# motorboardsurface.net
KiCad netlist of a schematic drawn in EAGLE
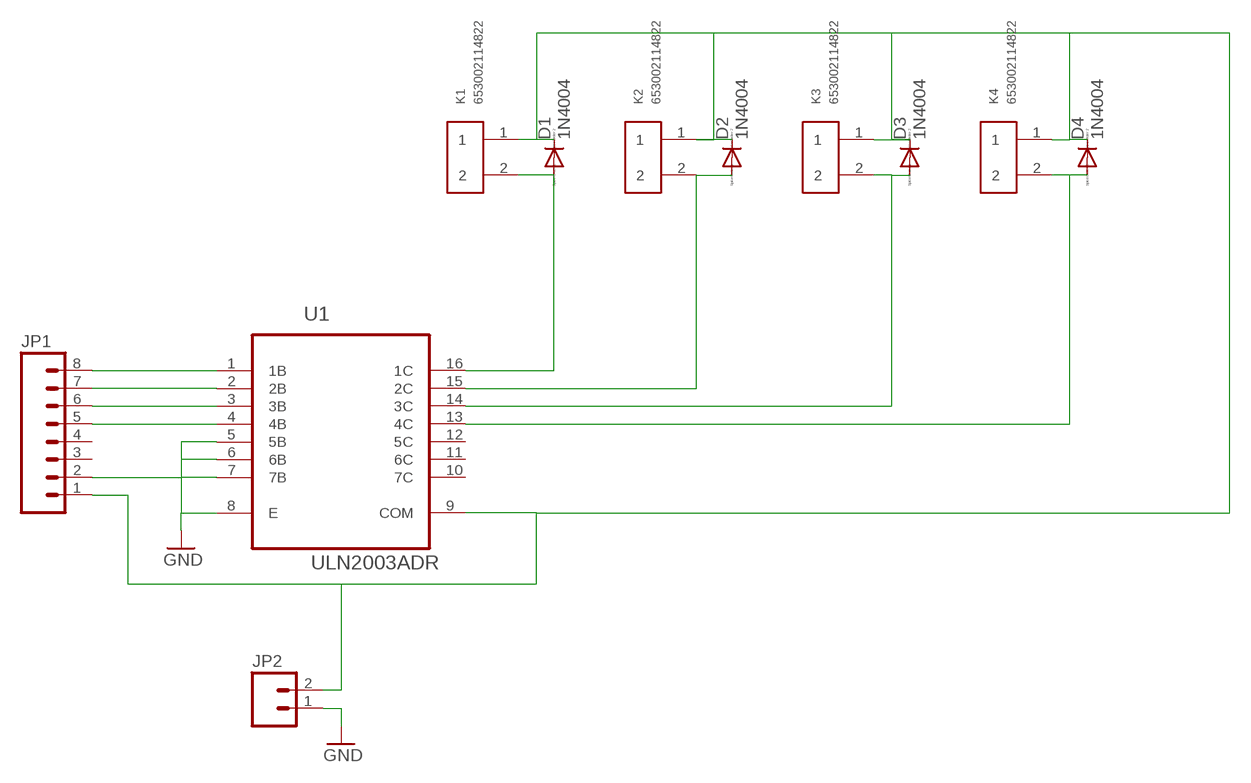
[diagram p0: schematic, sheet 1]

(export (version "E")
  (design (tool "Eeschema 10.0.6"))
  (components
    (comp (ref "D1")
      (value "1N4004")
      (footprint "eagle-import:DO41-10")
      (fields (field (name "MF") "NTE ELECTRONICS"))
      (libsource (lib "eagle-import") (part "1N4004"))
    )
    (comp (ref "D2")
      (value "1N4004")
      (footprint "eagle-import:DO41-10")
      (fields (field (name "MF") "NTE ELECTRONICS"))
      (libsource (lib "eagle-import") (part "1N4004"))
    )
    (comp (ref "D3")
      (value "1N4004")
      (footprint "eagle-import:DO41-10")
      (fields (field (name "MF") "NTE ELECTRONICS"))
      (libsource (lib "eagle-import") (part "1N4004"))
    )
    (comp (ref "D4")
      (value "1N4004")
      (footprint "eagle-import:DO41-10")
      (fields (field (name "MF") "NTE ELECTRONICS"))
      (libsource (lib "eagle-import") (part "1N4004"))
    )
    (comp (ref "JP1")
      (value "M08NO_SILK_FEMALE_PTH")
      (footprint "eagle-import:1X08_NO_SILK")
      (libsource (lib "eagle-import") (part "M08NO_SILK_FEMALE_PTH"))
    )
    (comp (ref "JP2")
      (value "M02LOCK_LONGPADS")
      (footprint "eagle-import:1X02_LOCK_LONGPADS")
      (libsource (lib "eagle-import") (part "M02LOCK_LONGPADS"))
    )
    (comp (ref "K1")
      (value "653002114822")
      (footprint "eagle-import:653002114822")
      (libsource (lib "eagle-import") (part "653002114822"))
    )
    (comp (ref "K2")
      (value "653002114822")
      (footprint "eagle-import:653002114822")
      (libsource (lib "eagle-import") (part "653002114822"))
    )
    (comp (ref "K3")
      (value "653002114822")
      (footprint "eagle-import:653002114822")
      (libsource (lib "eagle-import") (part "653002114822"))
    )
    (comp (ref "K4")
      (value "653002114822")
      (footprint "eagle-import:653002114822")
      (libsource (lib "eagle-import") (part "653002114822"))
    )
    (comp (ref "U1")
      (value "ULN2003ADR")
      (footprint "eagle-import:SOIC127P600X175-16N")
      (libsource (lib "eagle-import") (part "ULN2003ADR"))
    )
  )
  (nets
    (net (code "1") (name "GND") (class "Default")
      (node (ref "JP1") (pin "2") (pinfunction "2_2") (pintype "passive"))
      (node (ref "JP2") (pin "1") (pinfunction "1_1") (pintype "passive"))
      (node (ref "U1") (pin "5") (pinfunction "5B_5") (pintype "input"))
      (node (ref "U1") (pin "6") (pinfunction "6B_6") (pintype "input"))
      (node (ref "U1") (pin "7") (pinfunction "7B_7") (pintype "input"))
      (node (ref "U1") (pin "8") (pinfunction "E_8") (pintype "input"))
    )
    (net (code "2") (name "Net-(U1-1B)") (class "Default")
      (node (ref "JP1") (pin "8") (pinfunction "8_8") (pintype "passive"))
      (node (ref "U1") (pin "1") (pinfunction "1B_1") (pintype "input"))
    )
    (net (code "3") (name "Net-(U1-1C)") (class "Default")
      (node (ref "D1") (pin "A") (pinfunction "A_A") (pintype "passive"))
      (node (ref "K1") (pin "2") (pinfunction "2_2") (pintype "bidirectional"))
      (node (ref "U1") (pin "16") (pinfunction "1C_16") (pintype "output"))
    )
    (net (code "4") (name "Net-(U1-2B)") (class "Default")
      (node (ref "JP1") (pin "7") (pinfunction "7_7") (pintype "passive"))
      (node (ref "U1") (pin "2") (pinfunction "2B_2") (pintype "input"))
    )
    (net (code "5") (name "Net-(U1-2C)") (class "Default")
      (node (ref "D2") (pin "A") (pinfunction "A_A") (pintype "passive"))
      (node (ref "K2") (pin "2") (pinfunction "2_2") (pintype "bidirectional"))
      (node (ref "U1") (pin "15") (pinfunction "2C_15") (pintype "output"))
    )
    (net (code "6") (name "Net-(U1-3B)") (class "Default")
      (node (ref "JP1") (pin "6") (pinfunction "6_6") (pintype "passive"))
      (node (ref "U1") (pin "3") (pinfunction "3B_3") (pintype "input"))
    )
    (net (code "7") (name "Net-(U1-3C)") (class "Default")
      (node (ref "D3") (pin "A") (pinfunction "A_A") (pintype "passive"))
      (node (ref "K3") (pin "2") (pinfunction "2_2") (pintype "bidirectional"))
      (node (ref "U1") (pin "14") (pinfunction "3C_14") (pintype "output"))
    )
    (net (code "8") (name "Net-(U1-4B)") (class "Default")
      (node (ref "JP1") (pin "5") (pinfunction "5_5") (pintype "passive"))
      (node (ref "U1") (pin "4") (pinfunction "4B_4") (pintype "input"))
    )
    (net (code "9") (name "Net-(U1-4C)") (class "Default")
      (node (ref "D4") (pin "A") (pinfunction "A_A") (pintype "passive"))
      (node (ref "K4") (pin "2") (pinfunction "2_2") (pintype "bidirectional"))
      (node (ref "U1") (pin "13") (pinfunction "4C_13") (pintype "output"))
    )
    (net (code "10") (name "Net-(U1-COM)") (class "Default")
      (node (ref "D1") (pin "C") (pinfunction "C_C") (pintype "passive"))
      (node (ref "D2") (pin "C") (pinfunction "C_C") (pintype "passive"))
      (node (ref "D3") (pin "C") (pinfunction "C_C") (pintype "passive"))
      (node (ref "D4") (pin "C") (pinfunction "C_C") (pintype "passive"))
      (node (ref "JP1") (pin "1") (pinfunction "1_1") (pintype "passive"))
      (node (ref "JP2") (pin "2") (pinfunction "2_2") (pintype "passive"))
      (node (ref "K1") (pin "1") (pinfunction "1_1") (pintype "bidirectional"))
      (node (ref "K2") (pin "1") (pinfunction "1_1") (pintype "bidirectional"))
      (node (ref "K3") (pin "1") (pinfunction "1_1") (pintype "bidirectional"))
      (node (ref "K4") (pin "1") (pinfunction "1_1") (pintype "bidirectional"))
      (node (ref "U1") (pin "9") (pinfunction "COM_9") (pintype "output"))
    )
    (net (code "11") (name "unconnected-(JP1-Pad3)") (class "Default")
      (node (ref "JP1") (pin "3") (pinfunction "3_3") (pintype "passive"))
    )
    (net (code "12") (name "unconnected-(JP1-Pad4)") (class "Default")
      (node (ref "JP1") (pin "4") (pinfunction "4_4") (pintype "passive"))
    )
    (net (code "13") (name "unconnected-(U1-5C-Pad12)") (class "Default")
      (node (ref "U1") (pin "12") (pinfunction "5C_12") (pintype "output"))
    )
    (net (code "14") (name "unconnected-(U1-6C-Pad11)") (class "Default")
      (node (ref "U1") (pin "11") (pinfunction "6C_11") (pintype "output"))
    )
    (net (code "15") (name "unconnected-(U1-7C-Pad10)") (class "Default")
      (node (ref "U1") (pin "10") (pinfunction "7C_10") (pintype "output"))
    )
  )
)
